# 02-USER_IO.net
KiCad netlist of a schematic drawn in Altium Designer
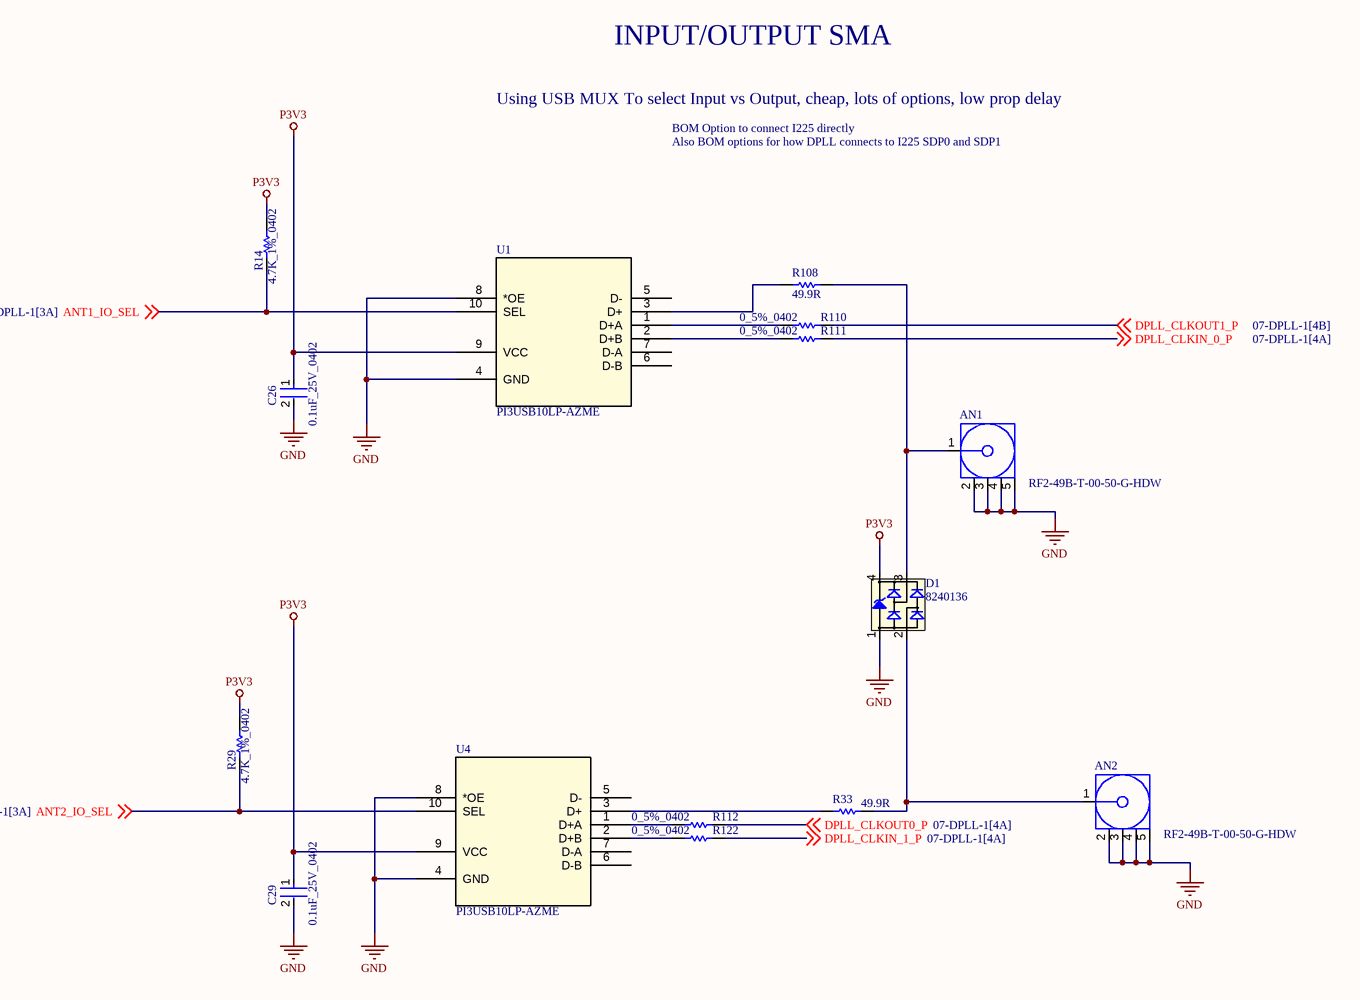
[diagram p0: 02-USER_IO.SchDoc]

(export (version "E")
  (design (tool "Eeschema 10.0.6"))
  (components
    (comp (ref "AN1")
      (value "RF2-49B-T-00-50-G-HDW")
      (footprint "AMPH-901-143-6RFX_V")
      (description "Coaxial connector, 50 Ohm, -65 to 165 degC, 5-Pin THD, RoHS, Bulk")
      (fields (field (name "MANUFACTURER") "Amphenol"))
      (libsource (lib "Altium Content Vault") (part "CN-S-4F-RF5"))
    )
    (comp (ref "AN2")
      (value "RF2-49B-T-00-50-G-HDW")
      (footprint "AMPH-901-143-6RFX_V")
      (description "Coaxial connector, 50 Ohm, -65 to 165 degC, 5-Pin THD, RoHS, Bulk")
      (fields (field (name "MANUFACTURER") "Amphenol"))
      (libsource (lib "Altium Content Vault") (part "CN-S-4F-RF5"))
    )
    (comp (ref "C26")
      (value "0.1uF_25V_0402")
      (footprint "FP-0402-L_1_0_1-W_0_5_0_1-IPC_C")
      (description "General Purpose Ceramic Capacitor, 0402, 100nF, 10%, X7R, 15%, 25V")
      (fields (field (name "VOLTAGE") "25V") (field (name "TOLERANCE") "10%"))
      (libsource (lib "Altium Content Vault") (part "b4654b650e69147ec39a6b967a45e02"))
    )
    (comp (ref "C29")
      (value "0.1uF_25V_0402")
      (footprint "FP-0402-L_1_0_1-W_0_5_0_1-IPC_C")
      (description "General Purpose Ceramic Capacitor, 0402, 100nF, 10%, X7R, 15%, 25V")
      (fields (field (name "VOLTAGE") "25V") (field (name "TOLERANCE") "10%"))
      (libsource (lib "Altium Content Vault") (part "b4654b650e69147ec39a6b967a45e02"))
    )
    (comp (ref "D1")
      (value "8240136")
      (footprint "SOT143-4L")
      (description "TVS Diode WE-TVS-HS, VRWM=3.3V")
      (fields (field (name "MANUFACTURER") "Wuerth Elektronik"))
      (libsource (lib "Altium Content Vault") (part "WE-TVS-HS-4"))
    )
    (comp (ref "R14")
      (value "4.7K_1%_0402")
      (footprint "RESC1005X40X25NL10T10")
      (fields (field (name "MANUFACTURER") "Bourns") (field (name "PART NUMBER") "CR0402-FX-4701GLF"))
      (libsource (lib "Altium Content Vault") (part "RES"))
    )
    (comp (ref "R29")
      (value "4.7K_1%_0402")
      (footprint "RESC1005X40X25NL10T10")
      (fields (field (name "MANUFACTURER") "Bourns") (field (name "PART NUMBER") "CR0402-FX-4701GLF"))
      (libsource (lib "Altium Content Vault") (part "RES"))
    )
    (comp (ref "R33")
      (value "49.9R")
      (footprint "RESC1608X55X25NL10T15")
      (libsource (lib "Altium Content Vault") (part "RES-2"))
    )
    (comp (ref "R108")
      (value "49.9R")
      (footprint "RESC1608X55X25NL10T15")
      (libsource (lib "Altium Content Vault") (part "RES-2"))
    )
    (comp (ref "R110")
      (value "0_5%_0402")
      (footprint "RESC1005X40X25LL10T10")
      (fields (field (name "MANUFACTURER") "KOA Speer") (field (name "PART NUMBER") "RK73Z1ETTP"))
      (libsource (lib "Altium Content Vault") (part "RES"))
    )
    (comp (ref "R111")
      (value "0_5%_0402")
      (footprint "RESC1005X40X25LL10T10")
      (fields (field (name "MANUFACTURER") "KOA Speer") (field (name "PART NUMBER") "RK73Z1ETTP"))
      (libsource (lib "Altium Content Vault") (part "RES"))
    )
    (comp (ref "R112")
      (value "0_5%_0402")
      (footprint "RESC1005X40X25LL10T10")
      (fields (field (name "MANUFACTURER") "KOA Speer") (field (name "PART NUMBER") "RK73Z1ETTP"))
      (libsource (lib "Altium Content Vault") (part "RES"))
    )
    (comp (ref "R122")
      (value "0_5%_0402")
      (footprint "RESC1005X40X25LL10T10")
      (fields (field (name "MANUFACTURER") "KOA Speer") (field (name "PART NUMBER") "RK73Z1ETTP"))
      (libsource (lib "Altium Content Vault") (part "RES"))
    )
    (comp (ref "U1")
      (value "PI3USB10LP-AZME")
      (footprint "ZM10_PER")
      (description "No Description Available")
      (libsource (lib "PI3USB10LP-AZME") (part "PI3USB10LP-AZME"))
    )
    (comp (ref "U4")
      (value "PI3USB10LP-AZME")
      (footprint "ZM10_PER")
      (description "No Description Available")
      (libsource (lib "PI3USB10LP-AZME") (part "PI3USB10LP-AZME"))
    )
  )
  (nets
    (net (code "1") (name "ANT1_IO_SEL") (class "Default")
      (node (ref "R14") (pin "2") (pinfunction "2_2") (pintype "passive"))
      (node (ref "U1") (pin "10") (pinfunction "SEL_10") (pintype "passive"))
    )
    (net (code "2") (name "ANT2_IO_SEL") (class "Default")
      (node (ref "R29") (pin "2") (pinfunction "2_2") (pintype "passive"))
      (node (ref "U4") (pin "10") (pinfunction "SEL_10") (pintype "passive"))
    )
    (net (code "3") (name "DPLL_CLKIN_0_P") (class "Default")
      (node (ref "R111") (pin "2") (pinfunction "2_2") (pintype "passive"))
    )
    (net (code "4") (name "DPLL_CLKIN_1_P") (class "Default")
      (node (ref "R122") (pin "2") (pinfunction "2_2") (pintype "passive"))
    )
    (net (code "5") (name "DPLL_CLKOUT0_P") (class "Default")
      (node (ref "R112") (pin "2") (pinfunction "2_2") (pintype "passive"))
    )
    (net (code "6") (name "DPLL_CLKOUT1_P") (class "Default")
      (node (ref "R110") (pin "2") (pinfunction "2_2") (pintype "passive"))
    )
    (net (code "7") (name "GND") (class "Default")
      (node (ref "AN1") (pin "2") (pinfunction "2_2") (pintype "passive"))
      (node (ref "AN1") (pin "3") (pinfunction "3_3") (pintype "passive"))
      (node (ref "AN1") (pin "4") (pinfunction "4_4") (pintype "passive"))
      (node (ref "AN1") (pin "5") (pinfunction "5_5") (pintype "passive"))
      (node (ref "AN2") (pin "2") (pinfunction "2_2") (pintype "passive"))
      (node (ref "AN2") (pin "3") (pinfunction "3_3") (pintype "passive"))
      (node (ref "AN2") (pin "4") (pinfunction "4_4") (pintype "passive"))
      (node (ref "AN2") (pin "5") (pinfunction "5_5") (pintype "passive"))
      (node (ref "C26") (pin "2") (pinfunction "2_2") (pintype "passive"))
      (node (ref "C29") (pin "2") (pinfunction "2_2") (pintype "passive"))
      (node (ref "D1") (pin "1") (pinfunction "GND_1") (pintype "passive"))
      (node (ref "U1") (pin "4") (pinfunction "GND_4") (pintype "power_in"))
      (node (ref "U1") (pin "8") (pinfunction "*OE_8") (pintype "passive"))
      (node (ref "U4") (pin "4") (pinfunction "GND_4") (pintype "power_in"))
      (node (ref "U4") (pin "8") (pinfunction "*OE_8") (pintype "passive"))
    )
    (net (code "8") (name "Net-(D1-I{slash}O1)") (class "Default")
      (node (ref "AN2") (pin "1") (pinfunction "1_1") (pintype "passive"))
      (node (ref "D1") (pin "2") (pinfunction "I/O1_2") (pintype "passive"))
      (node (ref "R33") (pin "2") (pinfunction "2_2") (pintype "passive"))
    )
    (net (code "9") (name "Net-(D1-I{slash}O2)") (class "Default")
      (node (ref "AN1") (pin "1") (pinfunction "1_1") (pintype "passive"))
      (node (ref "D1") (pin "3") (pinfunction "I/O2_3") (pintype "passive"))
      (node (ref "R108") (pin "1") (pinfunction "1_1") (pintype "passive"))
    )
    (net (code "10") (name "Net-(U1-D+)") (class "Default")
      (node (ref "R108") (pin "2") (pinfunction "2_2") (pintype "passive"))
      (node (ref "U1") (pin "3") (pinfunction "D+_3") (pintype "passive"))
    )
    (net (code "11") (name "Net-(U1-D+A)") (class "Default")
      (node (ref "R110") (pin "1") (pinfunction "1_1") (pintype "passive"))
      (node (ref "U1") (pin "1") (pinfunction "D+A_1") (pintype "passive"))
    )
    (net (code "12") (name "Net-(U1-D+B)") (class "Default")
      (node (ref "R111") (pin "1") (pinfunction "1_1") (pintype "passive"))
      (node (ref "U1") (pin "2") (pinfunction "D+B_2") (pintype "passive"))
    )
    (net (code "13") (name "Net-(U4-D+)") (class "Default")
      (node (ref "R33") (pin "1") (pinfunction "1_1") (pintype "passive"))
      (node (ref "U4") (pin "3") (pinfunction "D+_3") (pintype "passive"))
    )
    (net (code "14") (name "Net-(U4-D+A)") (class "Default")
      (node (ref "R112") (pin "1") (pinfunction "1_1") (pintype "passive"))
      (node (ref "U4") (pin "1") (pinfunction "D+A_1") (pintype "passive"))
    )
    (net (code "15") (name "Net-(U4-D+B)") (class "Default")
      (node (ref "R122") (pin "1") (pinfunction "1_1") (pintype "passive"))
      (node (ref "U4") (pin "2") (pinfunction "D+B_2") (pintype "passive"))
    )
    (net (code "16") (name "P3V3") (class "Default")
      (node (ref "C26") (pin "1") (pinfunction "1_1") (pintype "passive"))
      (node (ref "C29") (pin "1") (pinfunction "1_1") (pintype "passive"))
      (node (ref "D1") (pin "4") (pinfunction "VDD_4") (pintype "passive"))
      (node (ref "R14") (pin "1") (pinfunction "1_1") (pintype "passive"))
      (node (ref "R29") (pin "1") (pinfunction "1_1") (pintype "passive"))
      (node (ref "U1") (pin "9") (pinfunction "VCC_9") (pintype "power_in"))
      (node (ref "U4") (pin "9") (pinfunction "VCC_9") (pintype "power_in"))
    )
    (net (code "17") (name "unconnected-(U1-D--Pad5)") (class "Default")
      (node (ref "U1") (pin "5") (pinfunction "D-_5") (pintype "passive"))
    )
    (net (code "18") (name "unconnected-(U1-D-A-Pad7)") (class "Default")
      (node (ref "U1") (pin "7") (pinfunction "D-A_7") (pintype "passive"))
    )
    (net (code "19") (name "unconnected-(U1-D-B-Pad6)") (class "Default")
      (node (ref "U1") (pin "6") (pinfunction "D-B_6") (pintype "passive"))
    )
    (net (code "20") (name "unconnected-(U4-D--Pad5)") (class "Default")
      (node (ref "U4") (pin "5") (pinfunction "D-_5") (pintype "passive"))
    )
    (net (code "21") (name "unconnected-(U4-D-A-Pad7)") (class "Default")
      (node (ref "U4") (pin "7") (pinfunction "D-A_7") (pintype "passive"))
    )
    (net (code "22") (name "unconnected-(U4-D-B-Pad6)") (class "Default")
      (node (ref "U4") (pin "6") (pinfunction "D-B_6") (pintype "passive"))
    )
  )
)
